# AutoLevel_Module_V1_1.net
KiCad netlist of a schematic drawn in EAGLE
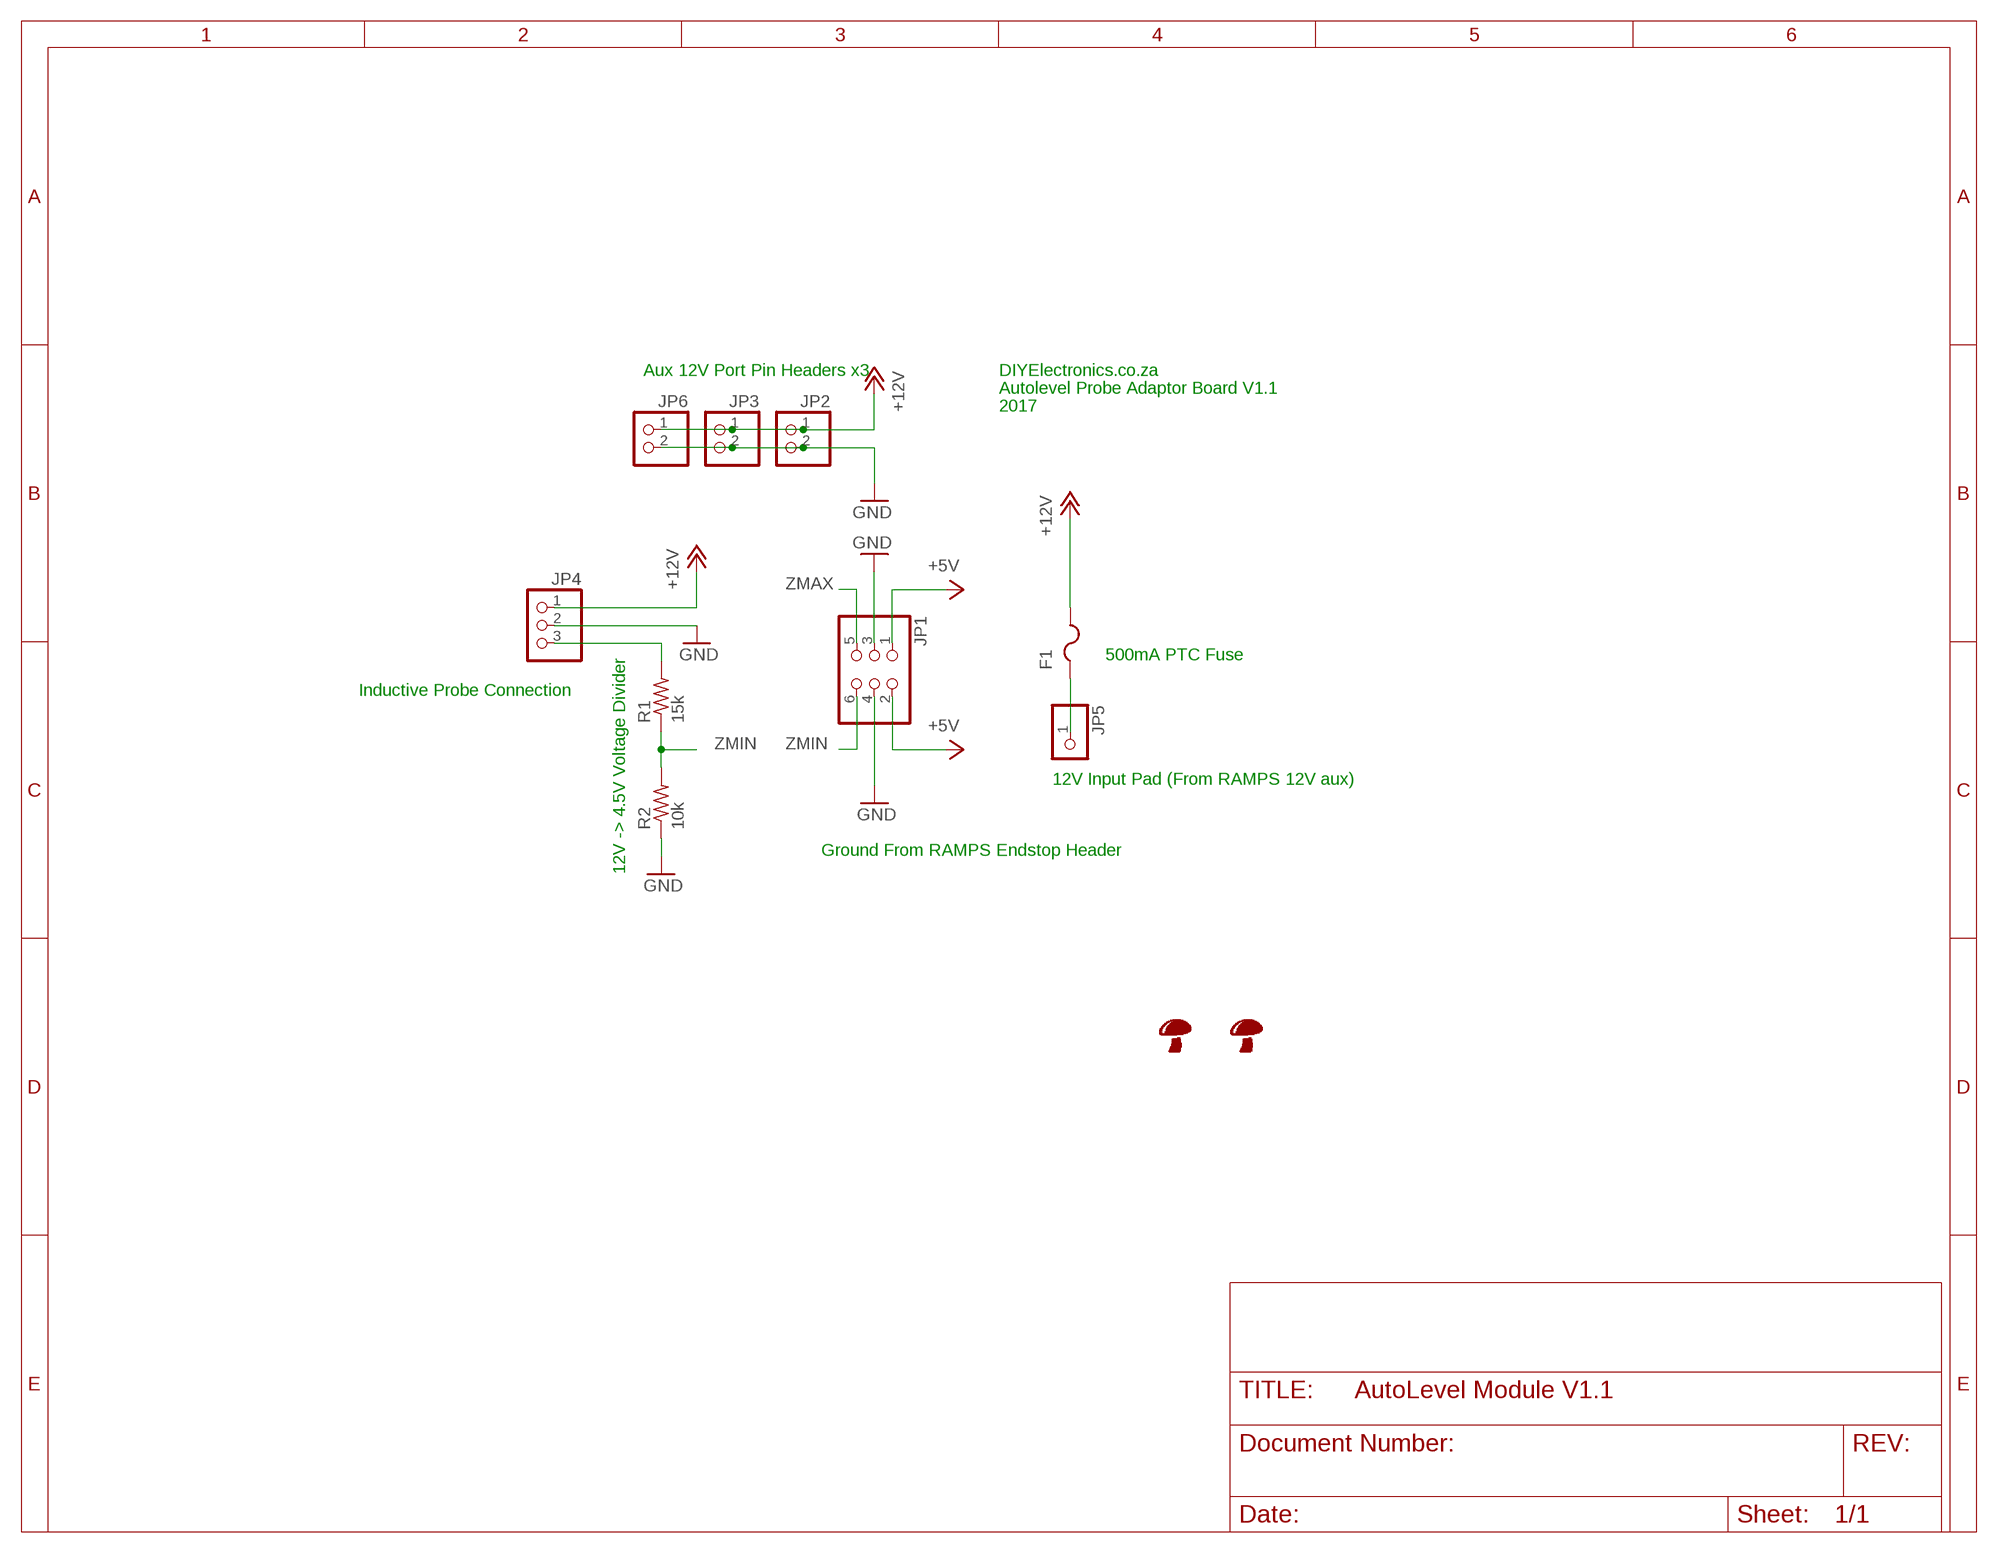
[diagram p0: schematic, sheet 1]

(export (version "E")
  (design (tool "Eeschema 10.0.6"))
  (components
    (comp (ref "F1")
      (value "PTCFUSE-1812")
      (footprint "eagle-import:1812")
      (libsource (lib "eagle-import") (part "PTCFUSE-1812"))
    )
    (comp (ref "JP1")
      (value "PINHD-2X3")
      (footprint "eagle-import:2X03")
      (libsource (lib "eagle-import") (part "PINHD-2X3"))
    )
    (comp (ref "JP2")
      (value "PINHD-1X2")
      (footprint "eagle-import:1X02")
      (libsource (lib "eagle-import") (part "PINHD-1X2"))
    )
    (comp (ref "JP3")
      (value "PINHD-1X2")
      (footprint "eagle-import:1X02")
      (libsource (lib "eagle-import") (part "PINHD-1X2"))
    )
    (comp (ref "JP4")
      (value "PINHD-1X3")
      (footprint "eagle-import:1X03")
      (libsource (lib "eagle-import") (part "PINHD-1X3"))
    )
    (comp (ref "JP5")
      (value "PINHD-1X1")
      (footprint "eagle-import:1X01")
      (libsource (lib "eagle-import") (part "PINHD-1X1"))
    )
    (comp (ref "JP6")
      (value "PINHD-1X2")
      (footprint "eagle-import:1X02")
      (libsource (lib "eagle-import") (part "PINHD-1X2"))
    )
    (comp (ref "R1")
      (value "15k")
      (footprint "eagle-import:R0805")
      (libsource (lib "eagle-import") (part "R-US_R0805"))
    )
    (comp (ref "R2")
      (value "10k")
      (footprint "eagle-import:R0805")
      (libsource (lib "eagle-import") (part "R-US_R0805"))
    )
    (comp (ref "U$1")
      (value "SHROOM5MM")
      (footprint "eagle-import:SHROOM")
      (libsource (lib "eagle-import") (part "SHROOM5MM"))
    )
    (comp (ref "U$2")
      (value "SHROOMBOTTOMSILK")
      (footprint "eagle-import:SHROOM_BS")
      (libsource (lib "eagle-import") (part "SHROOMBOTTOMSILK"))
    )
  )
  (nets
    (net (code "1") (name "+5V") (class "Default")
      (node (ref "JP1") (pin "1") (pinfunction "1_1") (pintype "passive"))
      (node (ref "JP1") (pin "2") (pinfunction "2_2") (pintype "passive"))
    )
    (net (code "2") (name "+12V") (class "Default")
      (node (ref "F1") (pin "2") (pinfunction "2_2") (pintype "passive"))
      (node (ref "JP2") (pin "1") (pinfunction "1_1") (pintype "passive"))
      (node (ref "JP3") (pin "1") (pinfunction "1_1") (pintype "passive"))
      (node (ref "JP4") (pin "1") (pinfunction "1_1") (pintype "passive"))
      (node (ref "JP6") (pin "1") (pinfunction "1_1") (pintype "passive"))
    )
    (net (code "3") (name "/ZMAX") (class "Default")
      (node (ref "JP1") (pin "5") (pinfunction "5_5") (pintype "passive"))
    )
    (net (code "4") (name "/ZMIN") (class "Default")
      (node (ref "JP1") (pin "6") (pinfunction "6_6") (pintype "passive"))
      (node (ref "R1") (pin "1") (pinfunction "1_1") (pintype "passive"))
      (node (ref "R2") (pin "2") (pinfunction "2_2") (pintype "passive"))
    )
    (net (code "5") (name "GND") (class "Default")
      (node (ref "JP1") (pin "3") (pinfunction "3_3") (pintype "passive"))
      (node (ref "JP1") (pin "4") (pinfunction "4_4") (pintype "passive"))
      (node (ref "JP2") (pin "2") (pinfunction "2_2") (pintype "passive"))
      (node (ref "JP3") (pin "2") (pinfunction "2_2") (pintype "passive"))
      (node (ref "JP4") (pin "2") (pinfunction "2_2") (pintype "passive"))
      (node (ref "JP6") (pin "2") (pinfunction "2_2") (pintype "passive"))
      (node (ref "R2") (pin "1") (pinfunction "1_1") (pintype "passive"))
    )
    (net (code "6") (name "Net-(F1-Pad1)") (class "Default")
      (node (ref "F1") (pin "1") (pinfunction "1_1") (pintype "passive"))
      (node (ref "JP5") (pin "1") (pinfunction "1_1") (pintype "passive"))
    )
    (net (code "7") (name "Net-(JP4-Pad3)") (class "Default")
      (node (ref "JP4") (pin "3") (pinfunction "3_3") (pintype "passive"))
      (node (ref "R1") (pin "2") (pinfunction "2_2") (pintype "passive"))
    )
  )
)
